# simple_fusion.net
KiCad netlist of a schematic drawn in EAGLE
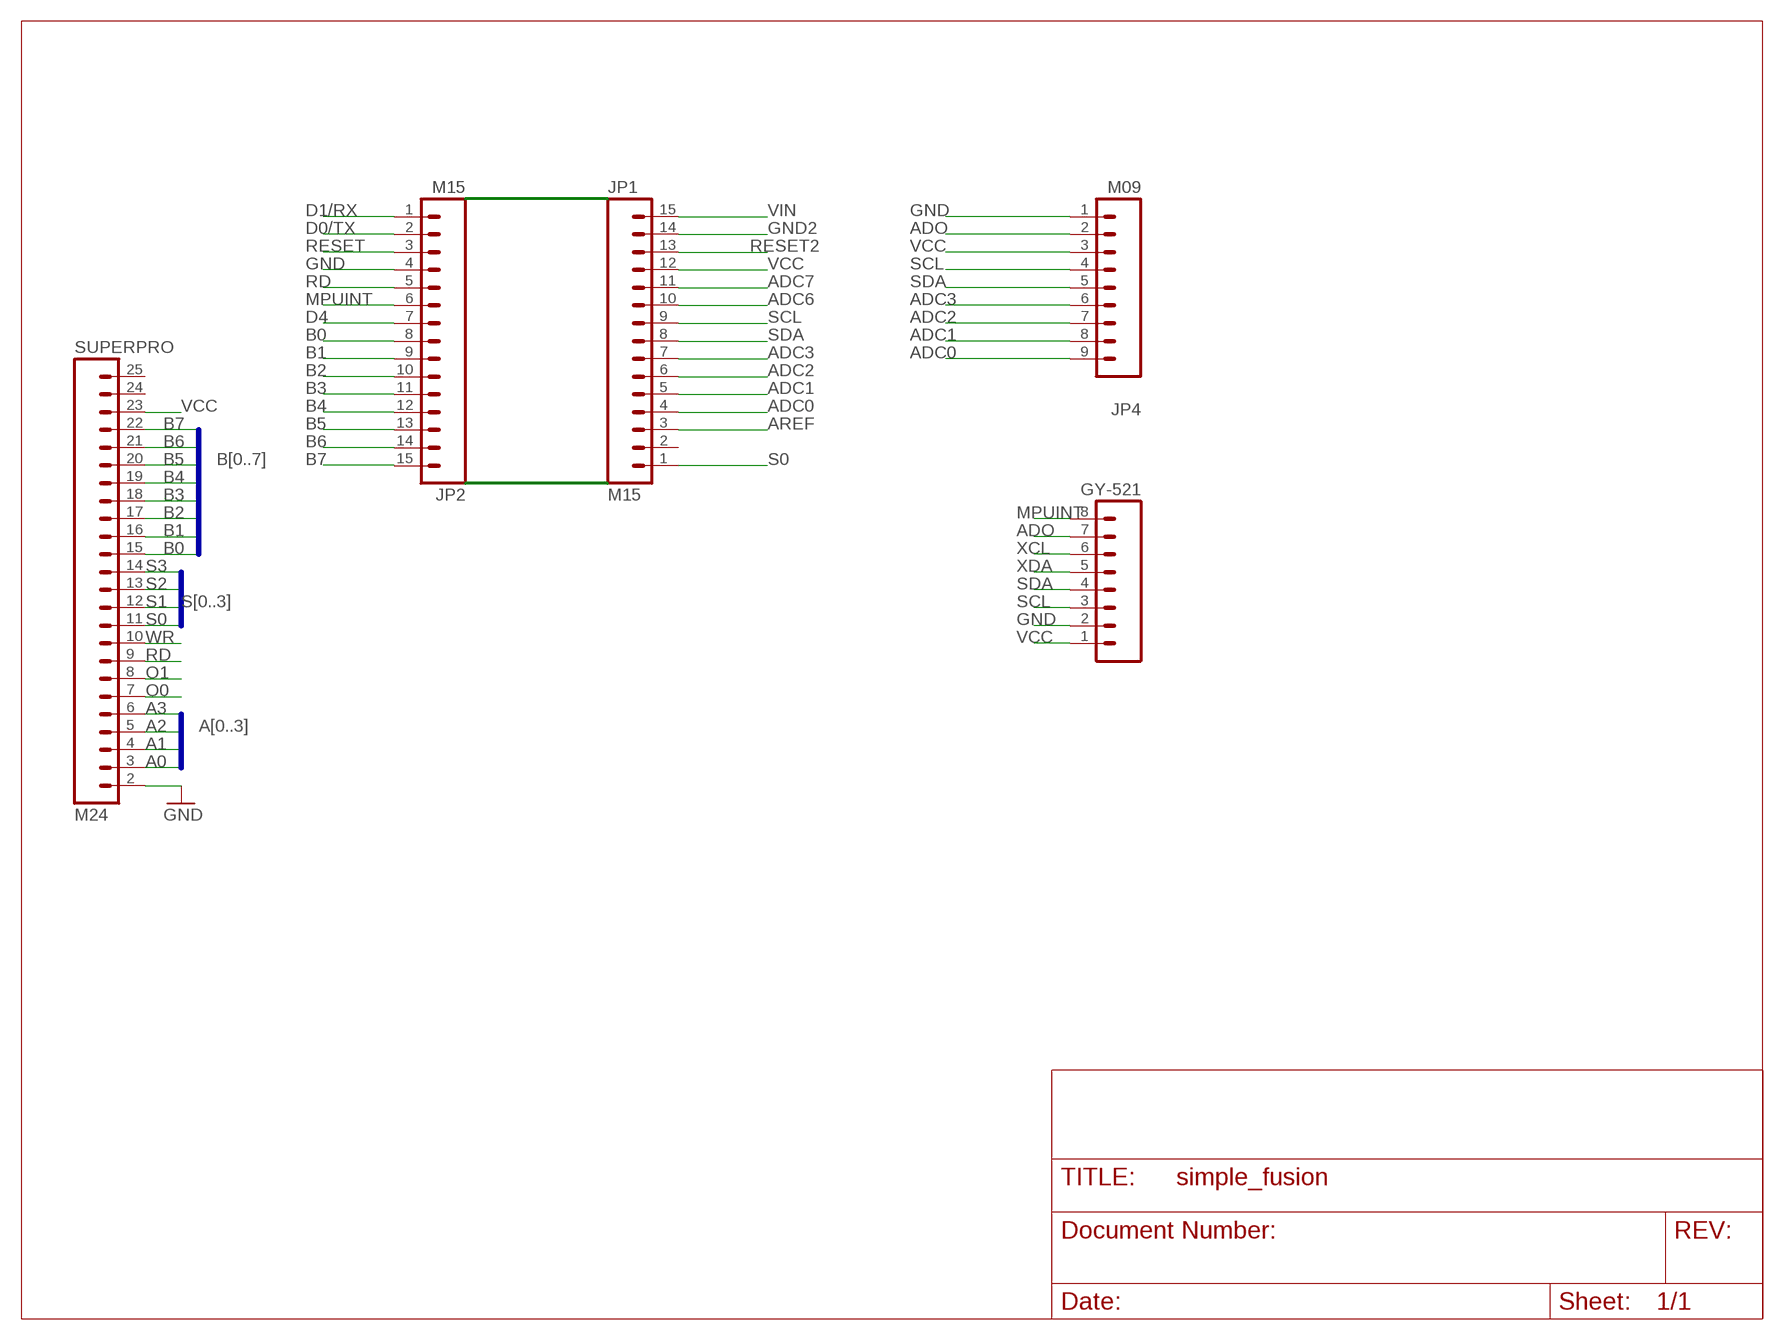
[diagram p0: schematic, sheet 1]

(export (version "E")
  (design (tool "Eeschema 10.0.6"))
  (components
    (comp (ref "GY-521")
      (value "M081X08")
      (footprint "eagle-import:1X08")
      (libsource (lib "eagle-import") (part "M081X08"))
    )
    (comp (ref "JP1")
      (value "M15")
      (footprint "eagle-import:1X15")
      (libsource (lib "eagle-import") (part "M15"))
    )
    (comp (ref "JP2")
      (value "M15")
      (footprint "eagle-import:1X15")
      (libsource (lib "eagle-import") (part "M15"))
    )
    (comp (ref "JP4")
      (value "M09")
      (footprint "eagle-import:1X09")
      (libsource (lib "eagle-import") (part "M09"))
    )
    (comp (ref "SUPERPRO")
      (value "M24")
      (footprint "eagle-import:1X24")
      (libsource (lib "eagle-import") (part "M24"))
    )
  )
  (nets
    (net (code "1") (name "/A0") (class "Default")
      (node (ref "SUPERPRO") (pin "3") (pinfunction "3_3") (pintype "passive"))
    )
    (net (code "2") (name "/A1") (class "Default")
      (node (ref "SUPERPRO") (pin "4") (pinfunction "4_4") (pintype "passive"))
    )
    (net (code "3") (name "/A2") (class "Default")
      (node (ref "SUPERPRO") (pin "5") (pinfunction "5_5") (pintype "passive"))
    )
    (net (code "4") (name "/A3") (class "Default")
      (node (ref "SUPERPRO") (pin "6") (pinfunction "6_6") (pintype "passive"))
    )
    (net (code "5") (name "/ADC0") (class "Default")
      (node (ref "JP1") (pin "4") (pinfunction "4_4") (pintype "passive"))
      (node (ref "JP4") (pin "9") (pinfunction "9_9") (pintype "passive"))
    )
    (net (code "6") (name "/ADC1") (class "Default")
      (node (ref "JP1") (pin "5") (pinfunction "5_5") (pintype "passive"))
      (node (ref "JP4") (pin "8") (pinfunction "8_8") (pintype "passive"))
    )
    (net (code "7") (name "/ADC2") (class "Default")
      (node (ref "JP1") (pin "6") (pinfunction "6_6") (pintype "passive"))
      (node (ref "JP4") (pin "7") (pinfunction "7_7") (pintype "passive"))
    )
    (net (code "8") (name "/ADC3") (class "Default")
      (node (ref "JP1") (pin "7") (pinfunction "7_7") (pintype "passive"))
      (node (ref "JP4") (pin "6") (pinfunction "6_6") (pintype "passive"))
    )
    (net (code "9") (name "/ADC6") (class "Default")
      (node (ref "JP1") (pin "10") (pinfunction "10_10") (pintype "passive"))
    )
    (net (code "10") (name "/ADC7") (class "Default")
      (node (ref "JP1") (pin "11") (pinfunction "11_11") (pintype "passive"))
    )
    (net (code "11") (name "/ADO") (class "Default")
      (node (ref "GY-521") (pin "7") (pinfunction "7_7") (pintype "passive"))
      (node (ref "JP4") (pin "2") (pinfunction "2_2") (pintype "passive"))
    )
    (net (code "12") (name "/AREF") (class "Default")
      (node (ref "JP1") (pin "3") (pinfunction "3_3") (pintype "passive"))
    )
    (net (code "14") (name "/B0") (class "Default")
      (node (ref "JP2") (pin "8") (pinfunction "8_8") (pintype "passive"))
      (node (ref "SUPERPRO") (pin "15") (pinfunction "15_15") (pintype "passive"))
    )
    (net (code "15") (name "/B1") (class "Default")
      (node (ref "JP2") (pin "9") (pinfunction "9_9") (pintype "passive"))
      (node (ref "SUPERPRO") (pin "16") (pinfunction "16_16") (pintype "passive"))
    )
    (net (code "16") (name "/B2") (class "Default")
      (node (ref "JP2") (pin "10") (pinfunction "10_10") (pintype "passive"))
      (node (ref "SUPERPRO") (pin "17") (pinfunction "17_17") (pintype "passive"))
    )
    (net (code "17") (name "/B3") (class "Default")
      (node (ref "JP2") (pin "11") (pinfunction "11_11") (pintype "passive"))
      (node (ref "SUPERPRO") (pin "18") (pinfunction "18_18") (pintype "passive"))
    )
    (net (code "18") (name "/B4") (class "Default")
      (node (ref "JP2") (pin "12") (pinfunction "12_12") (pintype "passive"))
      (node (ref "SUPERPRO") (pin "19") (pinfunction "19_19") (pintype "passive"))
    )
    (net (code "19") (name "/B5") (class "Default")
      (node (ref "JP2") (pin "13") (pinfunction "13_13") (pintype "passive"))
      (node (ref "SUPERPRO") (pin "20") (pinfunction "20_20") (pintype "passive"))
    )
    (net (code "20") (name "/B6") (class "Default")
      (node (ref "JP2") (pin "14") (pinfunction "14_14") (pintype "passive"))
      (node (ref "SUPERPRO") (pin "21") (pinfunction "21_21") (pintype "passive"))
    )
    (net (code "21") (name "/B7") (class "Default")
      (node (ref "JP2") (pin "15") (pinfunction "15_15") (pintype "passive"))
      (node (ref "SUPERPRO") (pin "22") (pinfunction "22_22") (pintype "passive"))
    )
    (net (code "23") (name "/D0{slash}TX") (class "Default")
      (node (ref "JP2") (pin "2") (pinfunction "2_2") (pintype "passive"))
    )
    (net (code "24") (name "/D1{slash}RX") (class "Default")
      (node (ref "JP2") (pin "1") (pinfunction "1_1") (pintype "passive"))
    )
    (net (code "25") (name "/D4") (class "Default")
      (node (ref "JP2") (pin "7") (pinfunction "7_7") (pintype "passive"))
    )
    (net (code "26") (name "/GND2") (class "Default")
      (node (ref "JP1") (pin "14") (pinfunction "14_14") (pintype "passive"))
    )
    (net (code "27") (name "/MPUINT") (class "Default")
      (node (ref "GY-521") (pin "8") (pinfunction "8_8") (pintype "passive"))
      (node (ref "JP2") (pin "6") (pinfunction "6_6") (pintype "passive"))
    )
    (net (code "29") (name "/O0") (class "Default")
      (node (ref "SUPERPRO") (pin "7") (pinfunction "7_7") (pintype "passive"))
    )
    (net (code "30") (name "/O1") (class "Default")
      (node (ref "SUPERPRO") (pin "8") (pinfunction "8_8") (pintype "passive"))
    )
    (net (code "31") (name "/RD") (class "Default")
      (node (ref "JP2") (pin "5") (pinfunction "5_5") (pintype "passive"))
      (node (ref "SUPERPRO") (pin "9") (pinfunction "9_9") (pintype "passive"))
    )
    (net (code "32") (name "/RESET") (class "Default")
      (node (ref "JP2") (pin "3") (pinfunction "3_3") (pintype "passive"))
    )
    (net (code "33") (name "/RESET2") (class "Default")
      (node (ref "JP1") (pin "13") (pinfunction "13_13") (pintype "passive"))
    )
    (net (code "34") (name "/S0") (class "Default")
      (node (ref "JP1") (pin "1") (pinfunction "1_1") (pintype "passive"))
      (node (ref "SUPERPRO") (pin "11") (pinfunction "11_11") (pintype "passive"))
    )
    (net (code "35") (name "/S1") (class "Default")
      (node (ref "SUPERPRO") (pin "12") (pinfunction "12_12") (pintype "passive"))
    )
    (net (code "36") (name "/S2") (class "Default")
      (node (ref "SUPERPRO") (pin "13") (pinfunction "13_13") (pintype "passive"))
    )
    (net (code "37") (name "/S3") (class "Default")
      (node (ref "SUPERPRO") (pin "14") (pinfunction "14_14") (pintype "passive"))
    )
    (net (code "38") (name "/SCL") (class "Default")
      (node (ref "GY-521") (pin "3") (pinfunction "3_3") (pintype "passive"))
      (node (ref "JP1") (pin "9") (pinfunction "9_9") (pintype "passive"))
      (node (ref "JP4") (pin "4") (pinfunction "4_4") (pintype "passive"))
    )
    (net (code "39") (name "/SDA") (class "Default")
      (node (ref "GY-521") (pin "4") (pinfunction "4_4") (pintype "passive"))
      (node (ref "JP1") (pin "8") (pinfunction "8_8") (pintype "passive"))
      (node (ref "JP4") (pin "5") (pinfunction "5_5") (pintype "passive"))
    )
    (net (code "41") (name "/VCC") (class "Default")
      (node (ref "GY-521") (pin "1") (pinfunction "1_1") (pintype "passive"))
      (node (ref "JP1") (pin "12") (pinfunction "12_12") (pintype "passive"))
      (node (ref "JP4") (pin "3") (pinfunction "3_3") (pintype "passive"))
      (node (ref "SUPERPRO") (pin "23") (pinfunction "23_23") (pintype "passive"))
    )
    (net (code "42") (name "/VIN") (class "Default")
      (node (ref "JP1") (pin "15") (pinfunction "15_15") (pintype "passive"))
    )
    (net (code "43") (name "/WR") (class "Default")
      (node (ref "SUPERPRO") (pin "10") (pinfunction "10_10") (pintype "passive"))
    )
    (net (code "44") (name "/XCL") (class "Default")
      (node (ref "GY-521") (pin "6") (pinfunction "6_6") (pintype "passive"))
    )
    (net (code "45") (name "/XDA") (class "Default")
      (node (ref "GY-521") (pin "5") (pinfunction "5_5") (pintype "passive"))
    )
    (net (code "46") (name "GND") (class "Default")
      (node (ref "GY-521") (pin "2") (pinfunction "2_2") (pintype "passive"))
      (node (ref "JP2") (pin "4") (pinfunction "4_4") (pintype "passive"))
      (node (ref "JP4") (pin "1") (pinfunction "1_1") (pintype "passive"))
      (node (ref "SUPERPRO") (pin "2") (pinfunction "2_2") (pintype "passive"))
    )
    (net (code "47") (name "unconnected-(JP1-Pad2)") (class "Default")
      (node (ref "JP1") (pin "2") (pinfunction "2_2") (pintype "passive"))
    )
    (net (code "48") (name "unconnected-(SUPERPRO-Pad24)") (class "Default")
      (node (ref "SUPERPRO") (pin "24") (pinfunction "24_24") (pintype "passive"))
    )
    (net (code "49") (name "unconnected-(SUPERPRO-Pad25)") (class "Default")
      (node (ref "SUPERPRO") (pin "25") (pinfunction "25_25") (pintype "passive"))
    )
  )
)
